# breakout.net
KiCad netlist of a schematic drawn in EAGLE
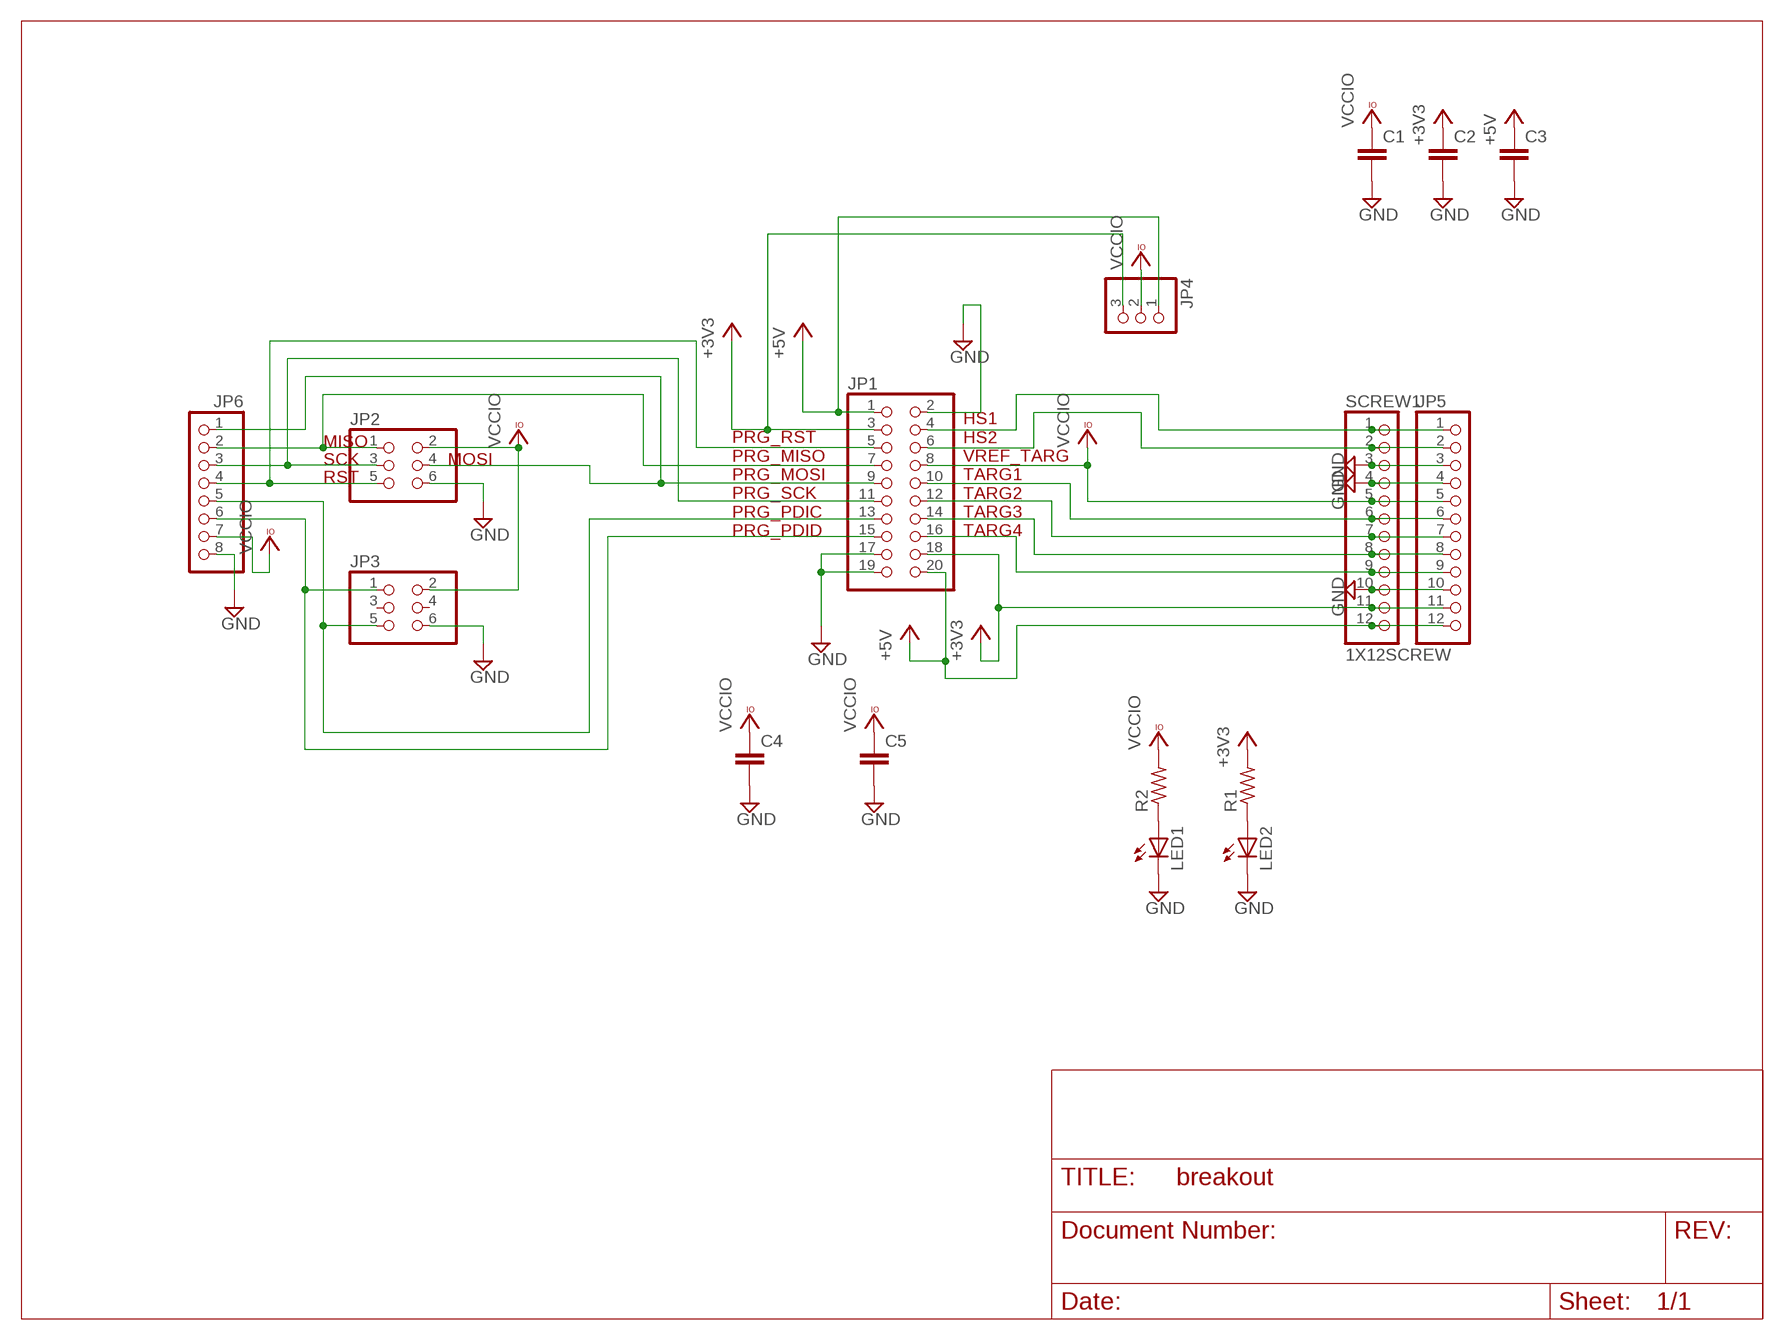
[diagram p0: schematic, sheet 1]

(export (version "E")
  (design (tool "Eeschema 10.0.6"))
  (components
    (comp (ref "C1")
      (value "C-EUC0805")
      (footprint "eagle-import:C0805")
      (libsource (lib "eagle-import") (part "C-EUC0805"))
    )
    (comp (ref "C2")
      (value "C-EUC0805")
      (footprint "eagle-import:C0805")
      (libsource (lib "eagle-import") (part "C-EUC0805"))
    )
    (comp (ref "C3")
      (value "C-EUC0805")
      (footprint "eagle-import:C0805")
      (libsource (lib "eagle-import") (part "C-EUC0805"))
    )
    (comp (ref "C4")
      (value "C-EUC0805")
      (footprint "eagle-import:C0805")
      (libsource (lib "eagle-import") (part "C-EUC0805"))
    )
    (comp (ref "C5")
      (value "C-EUC0805")
      (footprint "eagle-import:C0805")
      (libsource (lib "eagle-import") (part "C-EUC0805"))
    )
    (comp (ref "JP1")
      (value "PINHD-2X10")
      (footprint "eagle-import:2X10")
      (libsource (lib "eagle-import") (part "PINHD-2X10"))
    )
    (comp (ref "JP2")
      (value "PINHD-2X3")
      (footprint "eagle-import:2X03")
      (libsource (lib "eagle-import") (part "PINHD-2X3"))
    )
    (comp (ref "JP3")
      (value "PINHD-2X3")
      (footprint "eagle-import:2X03")
      (libsource (lib "eagle-import") (part "PINHD-2X3"))
    )
    (comp (ref "JP4")
      (value "PINHD-1X3")
      (footprint "eagle-import:1X03")
      (libsource (lib "eagle-import") (part "PINHD-1X3"))
    )
    (comp (ref "JP5")
      (value "PINHD-1X12")
      (footprint "eagle-import:1X12")
      (libsource (lib "eagle-import") (part "PINHD-1X12"))
    )
    (comp (ref "JP6")
      (value "PINHD-1X8")
      (footprint "eagle-import:1X08")
      (libsource (lib "eagle-import") (part "PINHD-1X8"))
    )
    (comp (ref "LED1")
      (value "LED3MM")
      (footprint "eagle-import:LED3MM")
      (libsource (lib "eagle-import") (part "LED3MM"))
    )
    (comp (ref "LED2")
      (value "LED3MM")
      (footprint "eagle-import:LED3MM")
      (libsource (lib "eagle-import") (part "LED3MM"))
    )
    (comp (ref "R1")
      (value "R-US_R0805")
      (footprint "eagle-import:R0805")
      (libsource (lib "eagle-import") (part "R-US_R0805"))
    )
    (comp (ref "R2")
      (value "R-US_R0805")
      (footprint "eagle-import:R0805")
      (libsource (lib "eagle-import") (part "R-US_R0805"))
    )
    (comp (ref "SCREW1")
      (value "1X12SCREW")
      (footprint "eagle-import:1X12_SCREW")
      (libsource (lib "eagle-import") (part "1X12SCREW"))
    )
  )
  (nets
    (net (code "1") (name "+3V3") (class "Default")
      (node (ref "C2") (pin "1") (pinfunction "1_1") (pintype "passive"))
      (node (ref "JP1") (pin "18") (pinfunction "18_18") (pintype "passive"))
      (node (ref "JP1") (pin "3") (pinfunction "3_3") (pintype "passive"))
      (node (ref "JP4") (pin "3") (pinfunction "3_3") (pintype "passive"))
      (node (ref "JP5") (pin "11") (pinfunction "11_11") (pintype "passive"))
      (node (ref "R1") (pin "2") (pinfunction "2_2") (pintype "passive"))
      (node (ref "SCREW1") (pin "11") (pinfunction "11_11") (pintype "passive"))
    )
    (net (code "2") (name "+5V") (class "Default")
      (node (ref "C3") (pin "1") (pinfunction "1_1") (pintype "passive"))
      (node (ref "JP1") (pin "1") (pinfunction "1_1") (pintype "passive"))
      (node (ref "JP1") (pin "20") (pinfunction "20_20") (pintype "passive"))
      (node (ref "JP4") (pin "1") (pinfunction "1_1") (pintype "passive"))
      (node (ref "JP5") (pin "12") (pinfunction "12_12") (pintype "passive"))
      (node (ref "SCREW1") (pin "12") (pinfunction "12_12") (pintype "passive"))
    )
    (net (code "3") (name "GND") (class "Default")
      (node (ref "C1") (pin "2") (pinfunction "2_2") (pintype "passive"))
      (node (ref "C2") (pin "2") (pinfunction "2_2") (pintype "passive"))
      (node (ref "C3") (pin "2") (pinfunction "2_2") (pintype "passive"))
      (node (ref "C4") (pin "2") (pinfunction "2_2") (pintype "passive"))
      (node (ref "C5") (pin "2") (pinfunction "2_2") (pintype "passive"))
      (node (ref "JP1") (pin "17") (pinfunction "17_17") (pintype "passive"))
      (node (ref "JP1") (pin "19") (pinfunction "19_19") (pintype "passive"))
      (node (ref "JP1") (pin "2") (pinfunction "2_2") (pintype "passive"))
      (node (ref "JP2") (pin "6") (pinfunction "6_6") (pintype "passive"))
      (node (ref "JP3") (pin "6") (pinfunction "6_6") (pintype "passive"))
      (node (ref "JP5") (pin "10") (pinfunction "10_10") (pintype "passive"))
      (node (ref "JP5") (pin "3") (pinfunction "3_3") (pintype "passive"))
      (node (ref "JP5") (pin "4") (pinfunction "4_4") (pintype "passive"))
      (node (ref "JP6") (pin "8") (pinfunction "8_8") (pintype "passive"))
      (node (ref "LED1") (pin "K") (pinfunction "C_K") (pintype "passive"))
      (node (ref "LED2") (pin "K") (pinfunction "C_K") (pintype "passive"))
      (node (ref "SCREW1") (pin "10") (pinfunction "10_10") (pintype "passive"))
      (node (ref "SCREW1") (pin "3") (pinfunction "3_3") (pintype "passive"))
      (node (ref "SCREW1") (pin "4") (pinfunction "4_4") (pintype "passive"))
    )
    (net (code "4") (name "Net-(JP1-Pad4)") (class "Default")
      (node (ref "JP1") (pin "4") (pinfunction "4_4") (pintype "passive"))
      (node (ref "JP5") (pin "1") (pinfunction "1_1") (pintype "passive"))
      (node (ref "SCREW1") (pin "1") (pinfunction "1_1") (pintype "passive"))
    )
    (net (code "5") (name "Net-(JP1-Pad5)") (class "Default")
      (node (ref "JP1") (pin "5") (pinfunction "5_5") (pintype "passive"))
      (node (ref "JP2") (pin "5") (pinfunction "5_5") (pintype "passive"))
      (node (ref "JP6") (pin "4") (pinfunction "4_4") (pintype "passive"))
    )
    (net (code "6") (name "Net-(JP1-Pad6)") (class "Default")
      (node (ref "JP1") (pin "6") (pinfunction "6_6") (pintype "passive"))
      (node (ref "JP5") (pin "2") (pinfunction "2_2") (pintype "passive"))
      (node (ref "SCREW1") (pin "2") (pinfunction "2_2") (pintype "passive"))
    )
    (net (code "7") (name "Net-(JP1-Pad7)") (class "Default")
      (node (ref "JP1") (pin "7") (pinfunction "7_7") (pintype "passive"))
      (node (ref "JP2") (pin "1") (pinfunction "1_1") (pintype "passive"))
      (node (ref "JP6") (pin "2") (pinfunction "2_2") (pintype "passive"))
    )
    (net (code "8") (name "Net-(JP1-Pad9)") (class "Default")
      (node (ref "JP1") (pin "9") (pinfunction "9_9") (pintype "passive"))
      (node (ref "JP2") (pin "4") (pinfunction "4_4") (pintype "passive"))
      (node (ref "JP6") (pin "1") (pinfunction "1_1") (pintype "passive"))
    )
    (net (code "9") (name "Net-(JP1-Pad10)") (class "Default")
      (node (ref "JP1") (pin "10") (pinfunction "10_10") (pintype "passive"))
      (node (ref "JP5") (pin "6") (pinfunction "6_6") (pintype "passive"))
      (node (ref "SCREW1") (pin "6") (pinfunction "6_6") (pintype "passive"))
    )
    (net (code "10") (name "Net-(JP1-Pad11)") (class "Default")
      (node (ref "JP1") (pin "11") (pinfunction "11_11") (pintype "passive"))
      (node (ref "JP2") (pin "3") (pinfunction "3_3") (pintype "passive"))
      (node (ref "JP6") (pin "3") (pinfunction "3_3") (pintype "passive"))
    )
    (net (code "11") (name "Net-(JP1-Pad12)") (class "Default")
      (node (ref "JP1") (pin "12") (pinfunction "12_12") (pintype "passive"))
      (node (ref "JP5") (pin "7") (pinfunction "7_7") (pintype "passive"))
      (node (ref "SCREW1") (pin "7") (pinfunction "7_7") (pintype "passive"))
    )
    (net (code "12") (name "Net-(JP1-Pad13)") (class "Default")
      (node (ref "JP1") (pin "13") (pinfunction "13_13") (pintype "passive"))
      (node (ref "JP3") (pin "5") (pinfunction "5_5") (pintype "passive"))
      (node (ref "JP6") (pin "5") (pinfunction "5_5") (pintype "passive"))
    )
    (net (code "13") (name "Net-(JP1-Pad14)") (class "Default")
      (node (ref "JP1") (pin "14") (pinfunction "14_14") (pintype "passive"))
      (node (ref "JP5") (pin "8") (pinfunction "8_8") (pintype "passive"))
      (node (ref "SCREW1") (pin "8") (pinfunction "8_8") (pintype "passive"))
    )
    (net (code "14") (name "Net-(JP1-Pad15)") (class "Default")
      (node (ref "JP1") (pin "15") (pinfunction "15_15") (pintype "passive"))
      (node (ref "JP3") (pin "1") (pinfunction "1_1") (pintype "passive"))
      (node (ref "JP6") (pin "6") (pinfunction "6_6") (pintype "passive"))
    )
    (net (code "15") (name "Net-(JP1-Pad16)") (class "Default")
      (node (ref "JP1") (pin "16") (pinfunction "16_16") (pintype "passive"))
      (node (ref "JP5") (pin "9") (pinfunction "9_9") (pintype "passive"))
      (node (ref "SCREW1") (pin "9") (pinfunction "9_9") (pintype "passive"))
    )
    (net (code "16") (name "Net-(LED1-PadA)") (class "Default")
      (node (ref "LED1") (pin "A") (pinfunction "A_A") (pintype "passive"))
      (node (ref "R2") (pin "1") (pinfunction "1_1") (pintype "passive"))
    )
    (net (code "17") (name "Net-(LED2-PadA)") (class "Default")
      (node (ref "LED2") (pin "A") (pinfunction "A_A") (pintype "passive"))
      (node (ref "R1") (pin "1") (pinfunction "1_1") (pintype "passive"))
    )
    (net (code "18") (name "VCCIO") (class "Default")
      (node (ref "C1") (pin "1") (pinfunction "1_1") (pintype "passive"))
      (node (ref "C4") (pin "1") (pinfunction "1_1") (pintype "passive"))
      (node (ref "C5") (pin "1") (pinfunction "1_1") (pintype "passive"))
      (node (ref "JP1") (pin "8") (pinfunction "8_8") (pintype "passive"))
      (node (ref "JP2") (pin "2") (pinfunction "2_2") (pintype "passive"))
      (node (ref "JP3") (pin "2") (pinfunction "2_2") (pintype "passive"))
      (node (ref "JP4") (pin "2") (pinfunction "2_2") (pintype "passive"))
      (node (ref "JP5") (pin "5") (pinfunction "5_5") (pintype "passive"))
      (node (ref "JP6") (pin "7") (pinfunction "7_7") (pintype "passive"))
      (node (ref "R2") (pin "2") (pinfunction "2_2") (pintype "passive"))
      (node (ref "SCREW1") (pin "5") (pinfunction "5_5") (pintype "passive"))
    )
    (net (code "19") (name "unconnected-(JP3-Pad3)") (class "Default")
      (node (ref "JP3") (pin "3") (pinfunction "3_3") (pintype "passive"))
    )
    (net (code "20") (name "unconnected-(JP3-Pad4)") (class "Default")
      (node (ref "JP3") (pin "4") (pinfunction "4_4") (pintype "passive"))
    )
  )
)
